# compute_module_power.net
KiCad netlist of a schematic drawn in Altium Designer
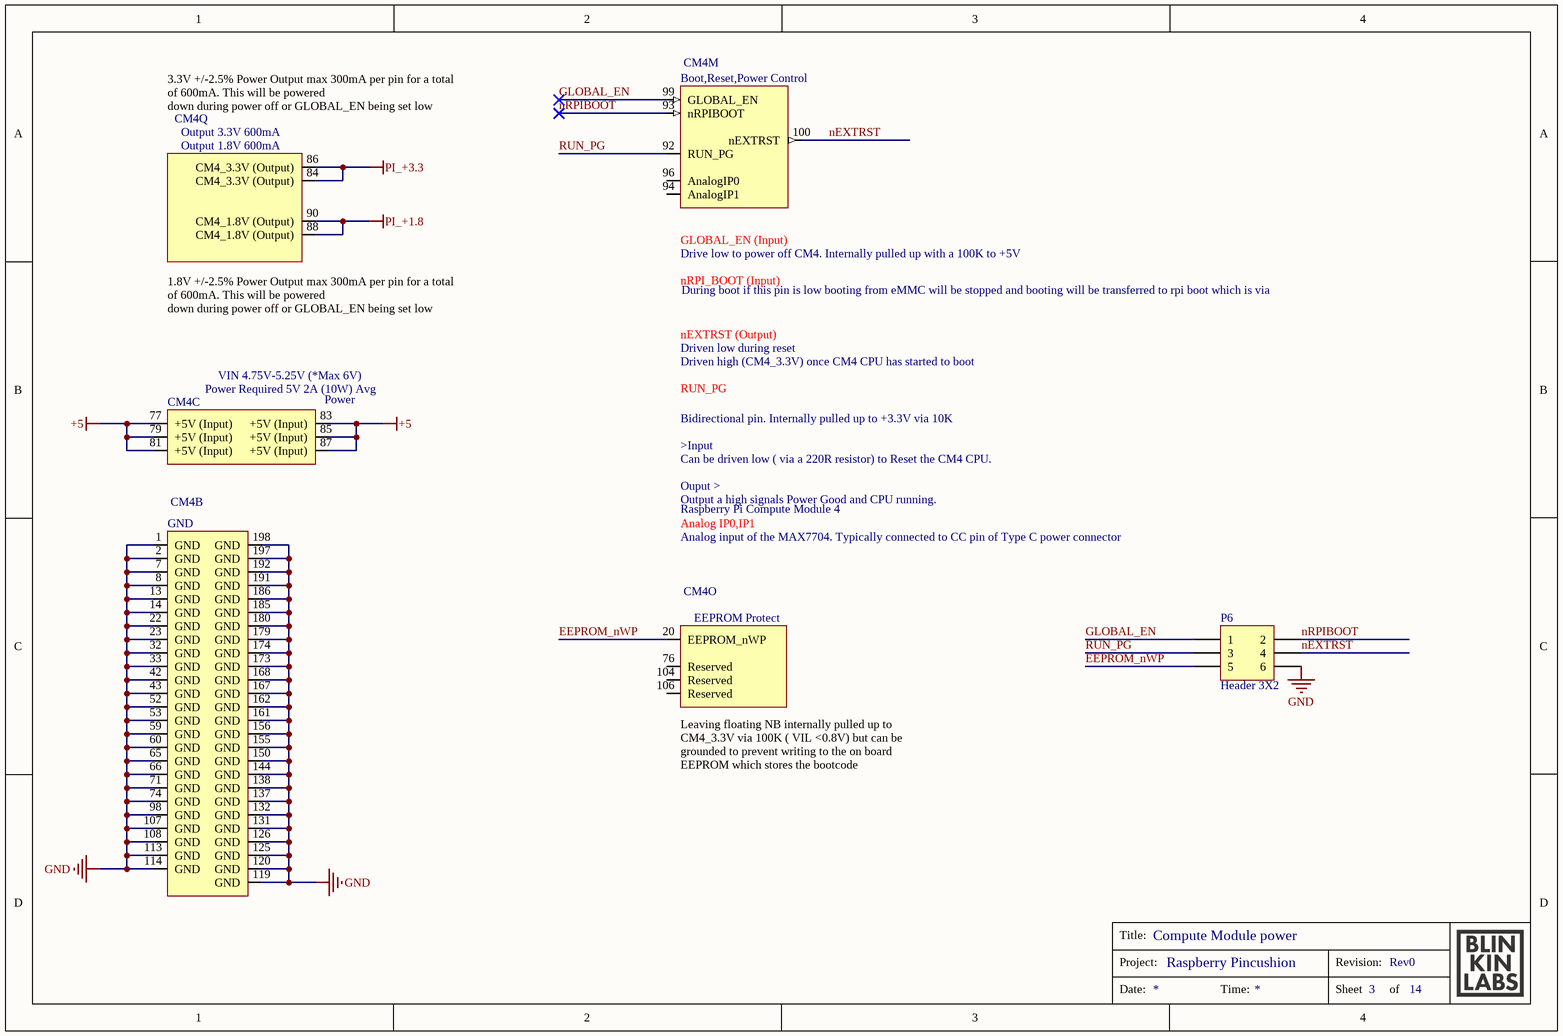
[diagram p0: compute module power.SchDoc]

(export (version "E")
  (design (tool "Eeschema 10.0.6"))
  (components
    (comp (ref "CM4")
      (value "Raspberry Pi Compute Module 4")
      (footprint "CM4-F40C-100DS-0.4v_1.5mm_0mm")
      (description "Raspberry Pi Compute Module 4 by Amornthep Phunsin")
      (libsource (lib "CM4") (part "CM4"))
    )
    (comp (ref "P6")
      (value "Header 3X2")
      (footprint "HDR2X3")
      (description "Header, 3-Pin, Dual row")
      (fields (field (name "PUBLISHER") "Altium Limited"))
      (libsource (lib "Miscellaneous Connectors") (part "Header 3X2"))
    )
  )
  (nets
    (net (code "1") (name "+5") (class "Default")
      (node (ref "CM4") (pin "77") (pinfunction "+5V_(Input)_77") (pintype "power_in"))
      (node (ref "CM4") (pin "79") (pinfunction "+5V_(Input)_79") (pintype "power_in"))
      (node (ref "CM4") (pin "81") (pinfunction "+5V_(Input)_81") (pintype "power_in"))
      (node (ref "CM4") (pin "83") (pinfunction "+5V_(Input)_83") (pintype "power_in"))
      (node (ref "CM4") (pin "85") (pinfunction "+5V_(Input)_85") (pintype "power_in"))
      (node (ref "CM4") (pin "87") (pinfunction "+5V_(Input)_87") (pintype "power_in"))
    )
    (net (code "2") (name "/EEPROM_nWP") (class "Default")
      (node (ref "CM4") (pin "20") (pinfunction "EEPROM_nWP_20") (pintype "passive"))
      (node (ref "P6") (pin "5") (pinfunction "5_5") (pintype "passive"))
    )
    (net (code "3") (name "/GLOBAL_EN") (class "Default")
      (node (ref "CM4") (pin "99") (pinfunction "GLOBAL_EN_99") (pintype "input"))
      (node (ref "P6") (pin "1") (pinfunction "1_1") (pintype "passive"))
    )
    (net (code "4") (name "/RUN_PG") (class "Default")
      (node (ref "CM4") (pin "92") (pinfunction "RUN_PG_92") (pintype "passive"))
      (node (ref "P6") (pin "3") (pinfunction "3_3") (pintype "passive"))
    )
    (net (code "5") (name "/nEXTRST") (class "Default")
      (node (ref "CM4") (pin "100") (pinfunction "nEXTRST_100") (pintype "output"))
      (node (ref "P6") (pin "4") (pinfunction "4_4") (pintype "passive"))
    )
    (net (code "6") (name "/nRPIBOOT") (class "Default")
      (node (ref "CM4") (pin "93") (pinfunction "nRPIBOOT_93") (pintype "input"))
      (node (ref "P6") (pin "2") (pinfunction "2_2") (pintype "passive"))
    )
    (net (code "7") (name "GND") (class "Default")
      (node (ref "CM4") (pin "1") (pinfunction "GND_1") (pintype "power_in"))
      (node (ref "CM4") (pin "107") (pinfunction "GND_107") (pintype "power_in"))
      (node (ref "CM4") (pin "108") (pinfunction "GND_108") (pintype "power_in"))
      (node (ref "CM4") (pin "113") (pinfunction "GND_113") (pintype "power_in"))
      (node (ref "CM4") (pin "114") (pinfunction "GND_114") (pintype "power_in"))
      (node (ref "CM4") (pin "119") (pinfunction "GND_119") (pintype "power_in"))
      (node (ref "CM4") (pin "120") (pinfunction "GND_120") (pintype "power_in"))
      (node (ref "CM4") (pin "125") (pinfunction "GND_125") (pintype "power_in"))
      (node (ref "CM4") (pin "126") (pinfunction "GND_126") (pintype "power_in"))
      (node (ref "CM4") (pin "13") (pinfunction "GND_13") (pintype "power_in"))
      (node (ref "CM4") (pin "131") (pinfunction "GND_131") (pintype "power_in"))
      (node (ref "CM4") (pin "132") (pinfunction "GND_132") (pintype "power_in"))
      (node (ref "CM4") (pin "137") (pinfunction "GND_137") (pintype "power_in"))
      (node (ref "CM4") (pin "138") (pinfunction "GND_138") (pintype "power_in"))
      (node (ref "CM4") (pin "14") (pinfunction "GND_14") (pintype "power_in"))
      (node (ref "CM4") (pin "144") (pinfunction "GND_144") (pintype "power_in"))
      (node (ref "CM4") (pin "150") (pinfunction "GND_150") (pintype "power_in"))
      (node (ref "CM4") (pin "155") (pinfunction "GND_155") (pintype "power_in"))
      (node (ref "CM4") (pin "156") (pinfunction "GND_156") (pintype "power_in"))
      (node (ref "CM4") (pin "161") (pinfunction "GND_161") (pintype "power_in"))
      (node (ref "CM4") (pin "162") (pinfunction "GND_162") (pintype "power_in"))
      (node (ref "CM4") (pin "167") (pinfunction "GND_167") (pintype "power_in"))
      (node (ref "CM4") (pin "168") (pinfunction "GND_168") (pintype "power_in"))
      (node (ref "CM4") (pin "173") (pinfunction "GND_173") (pintype "power_in"))
      (node (ref "CM4") (pin "174") (pinfunction "GND_174") (pintype "power_in"))
      (node (ref "CM4") (pin "179") (pinfunction "GND_179") (pintype "power_in"))
      (node (ref "CM4") (pin "180") (pinfunction "GND_180") (pintype "power_in"))
      (node (ref "CM4") (pin "185") (pinfunction "GND_185") (pintype "power_in"))
      (node (ref "CM4") (pin "186") (pinfunction "GND_186") (pintype "power_in"))
      (node (ref "CM4") (pin "191") (pinfunction "GND_191") (pintype "power_in"))
      (node (ref "CM4") (pin "192") (pinfunction "GND_192") (pintype "power_in"))
      (node (ref "CM4") (pin "197") (pinfunction "GND_197") (pintype "power_in"))
      (node (ref "CM4") (pin "198") (pinfunction "GND_198") (pintype "power_in"))
      (node (ref "CM4") (pin "2") (pinfunction "GND_2") (pintype "power_in"))
      (node (ref "CM4") (pin "22") (pinfunction "GND_22") (pintype "power_in"))
      (node (ref "CM4") (pin "23") (pinfunction "GND_23") (pintype "power_in"))
      (node (ref "CM4") (pin "32") (pinfunction "GND_32") (pintype "power_in"))
      (node (ref "CM4") (pin "33") (pinfunction "GND_33") (pintype "power_in"))
      (node (ref "CM4") (pin "42") (pinfunction "GND_42") (pintype "power_in"))
      (node (ref "CM4") (pin "43") (pinfunction "GND_43") (pintype "power_in"))
      (node (ref "CM4") (pin "52") (pinfunction "GND_52") (pintype "power_in"))
      (node (ref "CM4") (pin "53") (pinfunction "GND_53") (pintype "power_in"))
      (node (ref "CM4") (pin "59") (pinfunction "GND_59") (pintype "power_in"))
      (node (ref "CM4") (pin "60") (pinfunction "GND_60") (pintype "power_in"))
      (node (ref "CM4") (pin "65") (pinfunction "GND_65") (pintype "power_in"))
      (node (ref "CM4") (pin "66") (pinfunction "GND_66") (pintype "power_in"))
      (node (ref "CM4") (pin "7") (pinfunction "GND_7") (pintype "power_in"))
      (node (ref "CM4") (pin "71") (pinfunction "GND_71") (pintype "power_in"))
      (node (ref "CM4") (pin "74") (pinfunction "GND_74") (pintype "power_in"))
      (node (ref "CM4") (pin "8") (pinfunction "GND_8") (pintype "power_in"))
      (node (ref "CM4") (pin "98") (pinfunction "GND_98") (pintype "power_in"))
      (node (ref "P6") (pin "6") (pinfunction "6_6") (pintype "passive"))
    )
    (net (code "8") (name "PI_+1.8") (class "Default")
      (node (ref "CM4") (pin "88") (pinfunction "CM4_1.8V_(Output)_88") (pintype "power_in"))
      (node (ref "CM4") (pin "90") (pinfunction "CM4_1.8V_(Output)_90") (pintype "power_in"))
    )
    (net (code "9") (name "PI_+3.3") (class "Default")
      (node (ref "CM4") (pin "84") (pinfunction "CM4_3.3V_(Output)_84") (pintype "power_in"))
      (node (ref "CM4") (pin "86") (pinfunction "CM4_3.3V_(Output)_86") (pintype "power_in"))
    )
    (net (code "10") (name "unconnected-(CM4M-AnalogIP0-Pad96)") (class "Default")
      (node (ref "CM4") (pin "96") (pinfunction "AnalogIP0_96") (pintype "passive"))
    )
    (net (code "11") (name "unconnected-(CM4M-AnalogIP1-Pad94)") (class "Default")
      (node (ref "CM4") (pin "94") (pinfunction "AnalogIP1_94") (pintype "passive"))
    )
    (net (code "12") (name "unconnected-(CM4O-Reserved-Pad76)") (class "Default")
      (node (ref "CM4") (pin "76") (pinfunction "Reserved_76") (pintype "passive"))
    )
    (net (code "13") (name "unconnected-(CM4O-Reserved-Pad104)") (class "Default")
      (node (ref "CM4") (pin "104") (pinfunction "Reserved_104") (pintype "passive"))
    )
    (net (code "14") (name "unconnected-(CM4O-Reserved-Pad106)") (class "Default")
      (node (ref "CM4") (pin "106") (pinfunction "Reserved_106") (pintype "passive"))
    )
  )
)
